# USBDAC_pcm2706.net
KiCad netlist of a schematic drawn in Altium Designer
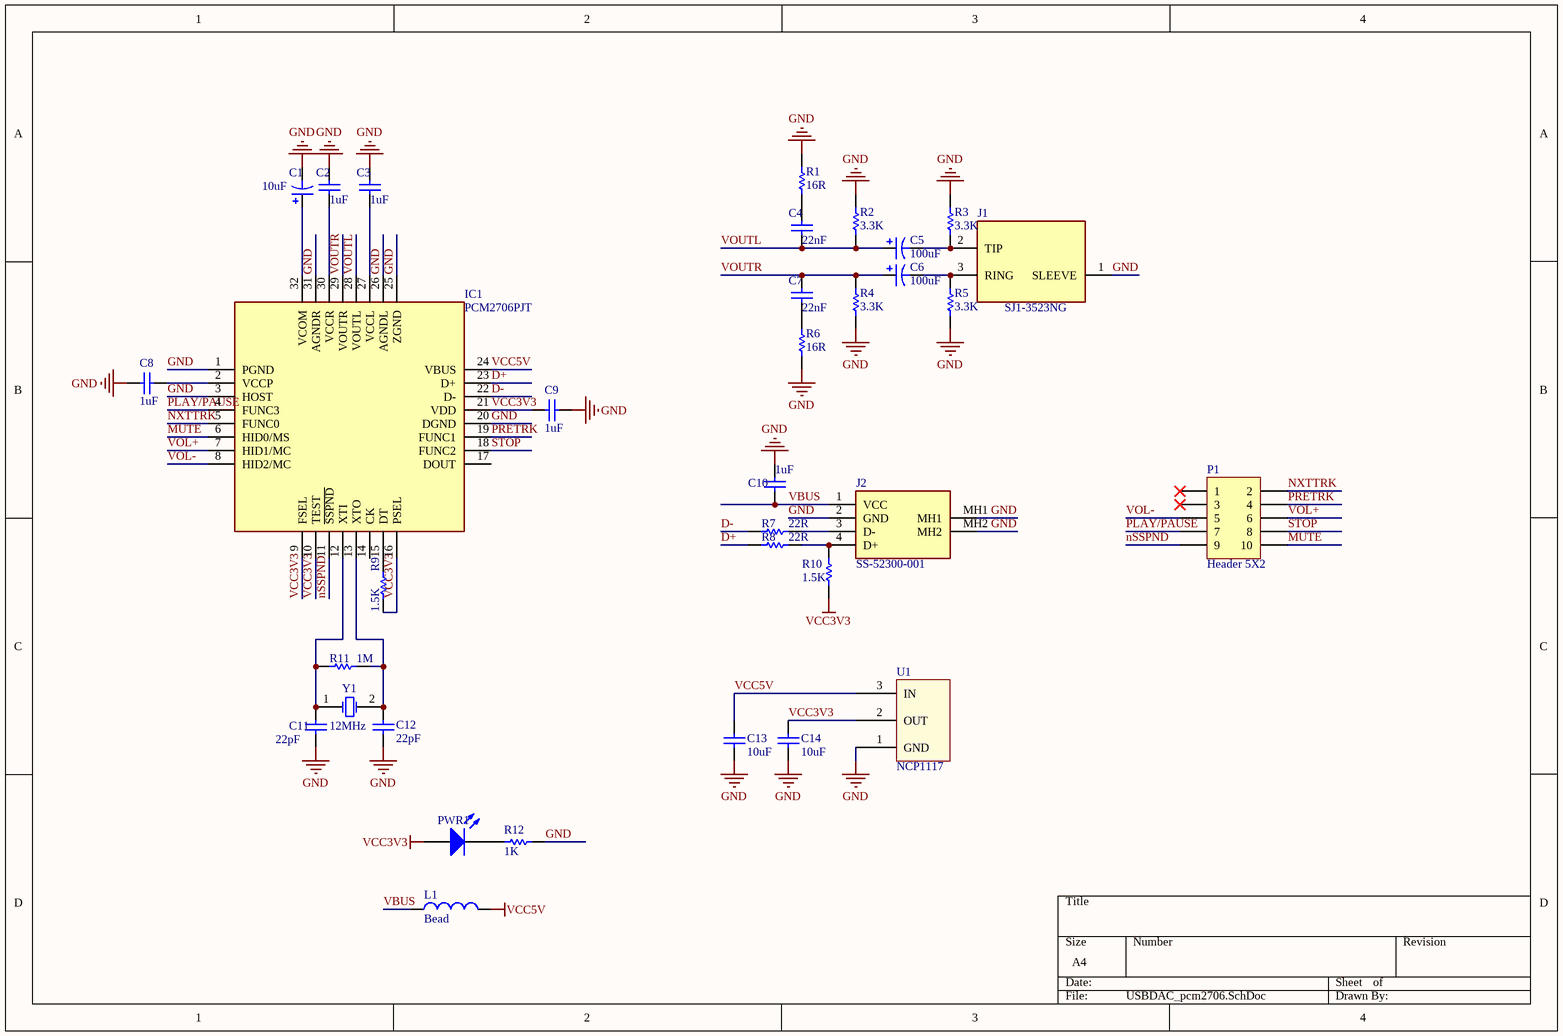
[diagram p0: USBDAC_pcm2706.SchDoc]

(export (version "E")
  (design (tool "Eeschema 10.0.6"))
  (components
    (comp (ref "C1")
      (value "10uF")
      (footprint "dip_cap")
      (description "Polarized Capacitor (Radial)")
      (fields (field (name "PUBLISHER") "Altium Limited"))
      (libsource (lib "Miscellaneous Devices") (part "Cap Pol1"))
    )
    (comp (ref "C2")
      (value "1uF")
      (footprint "SMD0805_CAP")
      (description "Capacitor (Semiconductor SIM Model)")
      (fields (field (name "PUBLISHER") "Altium Limited"))
      (libsource (lib "Miscellaneous Devices") (part "Cap Semi"))
    )
    (comp (ref "C3")
      (value "1uF")
      (footprint "SMD0805_CAP")
      (description "Capacitor (Semiconductor SIM Model)")
      (fields (field (name "PUBLISHER") "Altium Limited"))
      (libsource (lib "Miscellaneous Devices") (part "Cap Semi"))
    )
    (comp (ref "C4")
      (value "22nF")
      (footprint "SMD0805_CAP")
      (description "Capacitor (Semiconductor SIM Model)")
      (fields (field (name "PUBLISHER") "Altium Limited"))
      (libsource (lib "Miscellaneous Devices") (part "Cap Semi"))
    )
    (comp (ref "C5")
      (value "100uF")
      (footprint "dip_cap")
      (description "Polarized Capacitor (Radial)")
      (fields (field (name "PUBLISHER") "Altium Limited"))
      (libsource (lib "Miscellaneous Devices") (part "Cap Pol1"))
    )
    (comp (ref "C6")
      (value "100uF")
      (footprint "dip_cap")
      (description "Polarized Capacitor (Radial)")
      (fields (field (name "PUBLISHER") "Altium Limited"))
      (libsource (lib "Miscellaneous Devices") (part "Cap Pol1"))
    )
    (comp (ref "C7")
      (value "22nF")
      (footprint "SMD0805_CAP")
      (description "Capacitor (Semiconductor SIM Model)")
      (fields (field (name "PUBLISHER") "Altium Limited"))
      (libsource (lib "Miscellaneous Devices") (part "Cap Semi"))
    )
    (comp (ref "C8")
      (value "1uF")
      (footprint "SMD0805_CAP")
      (description "Capacitor (Semiconductor SIM Model)")
      (fields (field (name "PUBLISHER") "Altium Limited"))
      (libsource (lib "Miscellaneous Devices") (part "Cap Semi"))
    )
    (comp (ref "C9")
      (value "1uF")
      (footprint "SMD0805_CAP")
      (description "Capacitor (Semiconductor SIM Model)")
      (fields (field (name "PUBLISHER") "Altium Limited"))
      (libsource (lib "Miscellaneous Devices") (part "Cap Semi"))
    )
    (comp (ref "C10")
      (value "1uF")
      (footprint "SMD0805_CAP")
      (description "Capacitor (Semiconductor SIM Model)")
      (fields (field (name "PUBLISHER") "Altium Limited"))
      (libsource (lib "Miscellaneous Devices") (part "Cap Semi"))
    )
    (comp (ref "C11")
      (value "22pF")
      (footprint "SMD0805_CAP")
      (description "Capacitor (Semiconductor SIM Model)")
      (fields (field (name "PUBLISHER") "Altium Limited"))
      (libsource (lib "Miscellaneous Devices") (part "Cap Semi"))
    )
    (comp (ref "C12")
      (value "22pF")
      (footprint "SMD0805_CAP")
      (description "Capacitor (Semiconductor SIM Model)")
      (fields (field (name "PUBLISHER") "Altium Limited"))
      (libsource (lib "Miscellaneous Devices") (part "Cap Semi"))
    )
    (comp (ref "C13")
      (value "10uF")
      (footprint "SMD0805_CAP")
      (description "Capacitor (Semiconductor SIM Model)")
      (fields (field (name "PUBLISHER") "Altium Limited"))
      (libsource (lib "Miscellaneous Devices") (part "Cap Semi"))
    )
    (comp (ref "C14")
      (value "10uF")
      (footprint "SMD0805_CAP")
      (description "Capacitor (Semiconductor SIM Model)")
      (fields (field (name "PUBLISHER") "Altium Limited"))
      (libsource (lib "Miscellaneous Devices") (part "Cap Semi"))
    )
    (comp (ref "IC1")
      (value "PCM2706PJT")
      (footprint "usbdac_lib:QFP80P900X900X120-32N")
      (description "Integrated Circuit")
      (libsource (lib "usbdac_lib") (part "PCM2706PJT"))
    )
    (comp (ref "J1")
      (value "SJ1-3523NG")
      (footprint "usbdac_lib:SJ13523NG")
      (description "Connector")
      (libsource (lib "usbdac_lib") (part "SJ1-3523NG"))
    )
    (comp (ref "J2")
      (value "SS-52300-001")
      (footprint "usbdac_lib:SS52300001")
      (description "Connector")
      (libsource (lib "usbdac_lib") (part "SS-52300-001"))
    )
    (comp (ref "L1")
      (value "Bead")
      (footprint "SMD0805")
      (description "Inductor")
      (fields (field (name "PUBLISHER") "Altium Limited"))
      (libsource (lib "Miscellaneous Devices") (part "Inductor"))
    )
    (comp (ref "P1")
      (value "Header 5X2")
      (footprint "HDR2X5")
      (description "Header, 5-Pin, Dual row")
      (fields (field (name "PUBLISHER") "Altium Limited"))
      (libsource (lib "Miscellaneous Connectors") (part "Header 5X2"))
    )
    (comp (ref "PWR1")
      (value "LED0")
      (footprint "LED")
      (description "Typical INFRARED GaAs LED")
      (fields (field (name "PUBLISHER") "Altium Limited"))
      (libsource (lib "Miscellaneous Devices") (part "LED0"))
    )
    (comp (ref "R1")
      (value "16R")
      (footprint "SMD0805")
      (description "Semiconductor Resistor")
      (fields (field (name "Comment") "1K") (field (name "PUBLISHER") "Altium Limited"))
      (libsource (lib "Miscellaneous Devices") (part "Res Semi"))
    )
    (comp (ref "R2")
      (value "3.3K")
      (footprint "SMD0805")
      (description "Semiconductor Resistor")
      (fields (field (name "PUBLISHER") "Altium Limited"))
      (libsource (lib "Miscellaneous Devices") (part "Res Semi"))
    )
    (comp (ref "R3")
      (value "3.3K")
      (footprint "SMD0805")
      (description "Semiconductor Resistor")
      (fields (field (name "PUBLISHER") "Altium Limited"))
      (libsource (lib "Miscellaneous Devices") (part "Res Semi"))
    )
    (comp (ref "R4")
      (value "3.3K")
      (footprint "SMD0805")
      (description "Semiconductor Resistor")
      (fields (field (name "PUBLISHER") "Altium Limited"))
      (libsource (lib "Miscellaneous Devices") (part "Res Semi"))
    )
    (comp (ref "R5")
      (value "3.3K")
      (footprint "SMD0805")
      (description "Semiconductor Resistor")
      (fields (field (name "PUBLISHER") "Altium Limited"))
      (libsource (lib "Miscellaneous Devices") (part "Res Semi"))
    )
    (comp (ref "R6")
      (value "16R")
      (footprint "SMD0805")
      (description "Semiconductor Resistor")
      (fields (field (name "Comment") "1K") (field (name "PUBLISHER") "Altium Limited"))
      (libsource (lib "Miscellaneous Devices") (part "Res Semi"))
    )
    (comp (ref "R7")
      (value "22R")
      (footprint "SMD0805")
      (description "Semiconductor Resistor")
      (fields (field (name "PUBLISHER") "Altium Limited"))
      (libsource (lib "Miscellaneous Devices") (part "Res Semi"))
    )
    (comp (ref "R8")
      (value "22R")
      (footprint "SMD0805")
      (description "Semiconductor Resistor")
      (fields (field (name "PUBLISHER") "Altium Limited"))
      (libsource (lib "Miscellaneous Devices") (part "Res Semi"))
    )
    (comp (ref "R9")
      (value "1.5K")
      (footprint "SMD0805")
      (description "Semiconductor Resistor")
      (fields (field (name "PUBLISHER") "Altium Limited"))
      (libsource (lib "Miscellaneous Devices") (part "Res Semi"))
    )
    (comp (ref "R10")
      (value "1.5K")
      (footprint "SMD0805")
      (description "Semiconductor Resistor")
      (fields (field (name "PUBLISHER") "Altium Limited"))
      (libsource (lib "Miscellaneous Devices") (part "Res Semi"))
    )
    (comp (ref "R11")
      (value "1M")
      (footprint "SMD0805")
      (description "Semiconductor Resistor")
      (fields (field (name "PUBLISHER") "Altium Limited"))
      (libsource (lib "Miscellaneous Devices") (part "Res Semi"))
    )
    (comp (ref "R12")
      (value "1K")
      (footprint "SMD0805")
      (description "Semiconductor Resistor")
      (fields (field (name "PUBLISHER") "Altium Limited"))
      (libsource (lib "Miscellaneous Devices") (part "Res Semi"))
    )
    (comp (ref "U1")
      (value "NCP1117")
      (footprint "SOT-223-2")
      (description "IC REG 5V 1A DPAC")
      (libsource (lib "stm32_m3_component") (part "NCP1117"))
    )
    (comp (ref "Y1")
      (value "12MHz")
      (footprint "XTAL_DIP")
      (description "Crystal Oscillator 8MHz")
      (fields (field (name "PUBLISHER") "Altium Limited"))
      (libsource (lib "Miscellaneous Devices") (part "XTAL"))
    )
  )
  (nets
    (net (code "1") (name "/D+") (class "Default")
      (node (ref "IC1") (pin "23") (pinfunction "D+_23") (pintype "passive"))
      (node (ref "R8") (pin "1") (pinfunction "1_1") (pintype "passive"))
    )
    (net (code "2") (name "/D-") (class "Default")
      (node (ref "IC1") (pin "22") (pinfunction "D-_22") (pintype "passive"))
      (node (ref "R7") (pin "1") (pinfunction "1_1") (pintype "passive"))
    )
    (net (code "3") (name "/MUTE") (class "Default")
      (node (ref "IC1") (pin "6") (pinfunction "HID0/MS_6") (pintype "passive"))
      (node (ref "P1") (pin "10") (pinfunction "10_10") (pintype "passive"))
    )
    (net (code "4") (name "/NXTTRK") (class "Default")
      (node (ref "IC1") (pin "5") (pinfunction "FUNC0_5") (pintype "passive"))
      (node (ref "P1") (pin "2") (pinfunction "2_2") (pintype "passive"))
    )
    (net (code "5") (name "/PLAY{slash}PAUSE") (class "Default")
      (node (ref "IC1") (pin "4") (pinfunction "FUNC3_4") (pintype "passive"))
      (node (ref "P1") (pin "7") (pinfunction "7_7") (pintype "passive"))
    )
    (net (code "6") (name "/PRETRK") (class "Default")
      (node (ref "IC1") (pin "19") (pinfunction "FUNC1_19") (pintype "passive"))
      (node (ref "P1") (pin "4") (pinfunction "4_4") (pintype "passive"))
    )
    (net (code "7") (name "/STOP") (class "Default")
      (node (ref "IC1") (pin "18") (pinfunction "FUNC2_18") (pintype "passive"))
      (node (ref "P1") (pin "8") (pinfunction "8_8") (pintype "passive"))
    )
    (net (code "8") (name "/VBUS") (class "Default")
      (node (ref "C10") (pin "2") (pinfunction "2_2") (pintype "passive"))
      (node (ref "J2") (pin "1") (pinfunction "VCC_1") (pintype "passive"))
      (node (ref "L1") (pin "1") (pinfunction "1_1") (pintype "passive"))
    )
    (net (code "9") (name "/VOL+") (class "Default")
      (node (ref "IC1") (pin "7") (pinfunction "HID1/MC_7") (pintype "passive"))
      (node (ref "P1") (pin "6") (pinfunction "6_6") (pintype "passive"))
    )
    (net (code "10") (name "/VOL-") (class "Default")
      (node (ref "IC1") (pin "8") (pinfunction "HID2/MC_8") (pintype "passive"))
      (node (ref "P1") (pin "5") (pinfunction "5_5") (pintype "passive"))
    )
    (net (code "11") (name "/VOUTL") (class "Default")
      (node (ref "C4") (pin "1") (pinfunction "1_1") (pintype "passive"))
      (node (ref "C5") (pin "1") (pinfunction "1_1") (pintype "passive"))
      (node (ref "IC1") (pin "28") (pinfunction "VOUTL_28") (pintype "passive"))
      (node (ref "R2") (pin "1") (pinfunction "1_1") (pintype "passive"))
    )
    (net (code "12") (name "/VOUTR") (class "Default")
      (node (ref "C6") (pin "1") (pinfunction "1_1") (pintype "passive"))
      (node (ref "C7") (pin "1") (pinfunction "1_1") (pintype "passive"))
      (node (ref "IC1") (pin "29") (pinfunction "VOUTR_29") (pintype "passive"))
      (node (ref "R4") (pin "2") (pinfunction "2_2") (pintype "passive"))
    )
    (net (code "13") (name "/nSSPND") (class "Default")
      (node (ref "IC1") (pin "11") (pinfunction "~{SSPND}_11") (pintype "passive"))
      (node (ref "P1") (pin "9") (pinfunction "9_9") (pintype "passive"))
    )
    (net (code "14") (name "GND") (class "Default")
      (node (ref "C1") (pin "2") (pinfunction "2_2") (pintype "passive"))
      (node (ref "C10") (pin "1") (pinfunction "1_1") (pintype "passive"))
      (node (ref "C11") (pin "2") (pinfunction "2_2") (pintype "passive"))
      (node (ref "C12") (pin "2") (pinfunction "2_2") (pintype "passive"))
      (node (ref "C13") (pin "1") (pinfunction "1_1") (pintype "passive"))
      (node (ref "C14") (pin "1") (pinfunction "1_1") (pintype "passive"))
      (node (ref "C2") (pin "1") (pinfunction "1_1") (pintype "passive"))
      (node (ref "C3") (pin "1") (pinfunction "1_1") (pintype "passive"))
      (node (ref "C8") (pin "1") (pinfunction "1_1") (pintype "passive"))
      (node (ref "C9") (pin "1") (pinfunction "1_1") (pintype "passive"))
      (node (ref "IC1") (pin "1") (pinfunction "PGND_1") (pintype "passive"))
      (node (ref "IC1") (pin "20") (pinfunction "DGND_20") (pintype "passive"))
      (node (ref "IC1") (pin "25") (pinfunction "ZGND_25") (pintype "passive"))
      (node (ref "IC1") (pin "26") (pinfunction "AGNDL_26") (pintype "passive"))
      (node (ref "IC1") (pin "3") (pinfunction "HOST_3") (pintype "passive"))
      (node (ref "IC1") (pin "31") (pinfunction "AGNDR_31") (pintype "passive"))
      (node (ref "J1") (pin "1") (pinfunction "SLEEVE_1") (pintype "passive"))
      (node (ref "J2") (pin "2") (pinfunction "GND_2") (pintype "passive"))
      (node (ref "J2") (pin "MH1") (pinfunction "MH1_MH1") (pintype "passive"))
      (node (ref "J2") (pin "MH2") (pinfunction "MH2_MH2") (pintype "passive"))
      (node (ref "R1") (pin "2") (pinfunction "2_2") (pintype "passive"))
      (node (ref "R12") (pin "1") (pinfunction "1_1") (pintype "passive"))
      (node (ref "R2") (pin "2") (pinfunction "2_2") (pintype "passive"))
      (node (ref "R3") (pin "2") (pinfunction "2_2") (pintype "passive"))
      (node (ref "R4") (pin "1") (pinfunction "1_1") (pintype "passive"))
      (node (ref "R5") (pin "1") (pinfunction "1_1") (pintype "passive"))
      (node (ref "R6") (pin "2") (pinfunction "2_2") (pintype "passive"))
      (node (ref "U1") (pin "1") (pinfunction "GND_1") (pintype "passive"))
    )
    (net (code "15") (name "Net-(C4-Pad2)") (class "Default")
      (node (ref "C4") (pin "2") (pinfunction "2_2") (pintype "passive"))
      (node (ref "R1") (pin "1") (pinfunction "1_1") (pintype "passive"))
    )
    (net (code "16") (name "Net-(C7-Pad2)") (class "Default")
      (node (ref "C7") (pin "2") (pinfunction "2_2") (pintype "passive"))
      (node (ref "R6") (pin "1") (pinfunction "1_1") (pintype "passive"))
    )
    (net (code "17") (name "Net-(IC1-DT)") (class "Default")
      (node (ref "IC1") (pin "15") (pinfunction "DT_15") (pintype "passive"))
      (node (ref "R9") (pin "2") (pinfunction "2_2") (pintype "passive"))
    )
    (net (code "18") (name "Net-(IC1-VCCL)") (class "Default")
      (node (ref "C3") (pin "2") (pinfunction "2_2") (pintype "passive"))
      (node (ref "IC1") (pin "27") (pinfunction "VCCL_27") (pintype "passive"))
    )
    (net (code "19") (name "Net-(IC1-VCCP)") (class "Default")
      (node (ref "C8") (pin "2") (pinfunction "2_2") (pintype "passive"))
      (node (ref "IC1") (pin "2") (pinfunction "VCCP_2") (pintype "passive"))
    )
    (net (code "20") (name "Net-(IC1-VCCR)") (class "Default")
      (node (ref "C2") (pin "2") (pinfunction "2_2") (pintype "passive"))
      (node (ref "IC1") (pin "30") (pinfunction "VCCR_30") (pintype "passive"))
    )
    (net (code "21") (name "Net-(IC1-VCOM)") (class "Default")
      (node (ref "C1") (pin "1") (pinfunction "1_1") (pintype "passive"))
      (node (ref "IC1") (pin "32") (pinfunction "VCOM_32") (pintype "passive"))
    )
    (net (code "22") (name "Net-(IC1-XTI)") (class "Default")
      (node (ref "C11") (pin "1") (pinfunction "1_1") (pintype "passive"))
      (node (ref "IC1") (pin "12") (pinfunction "XTI_12") (pintype "passive"))
      (node (ref "R11") (pin "1") (pinfunction "1_1") (pintype "passive"))
      (node (ref "Y1") (pin "1") (pinfunction "OSC1_1") (pintype "passive"))
    )
    (net (code "23") (name "Net-(IC1-XTO)") (class "Default")
      (node (ref "C12") (pin "1") (pinfunction "1_1") (pintype "passive"))
      (node (ref "IC1") (pin "13") (pinfunction "XTO_13") (pintype "passive"))
      (node (ref "R11") (pin "2") (pinfunction "2_2") (pintype "passive"))
      (node (ref "Y1") (pin "2") (pinfunction "OSC2_2") (pintype "passive"))
    )
    (net (code "24") (name "Net-(J1-RING)") (class "Default")
      (node (ref "C6") (pin "2") (pinfunction "2_2") (pintype "passive"))
      (node (ref "J1") (pin "3") (pinfunction "RING_3") (pintype "passive"))
      (node (ref "R5") (pin "2") (pinfunction "2_2") (pintype "passive"))
    )
    (net (code "25") (name "Net-(J1-TIP)") (class "Default")
      (node (ref "C5") (pin "2") (pinfunction "2_2") (pintype "passive"))
      (node (ref "J1") (pin "2") (pinfunction "TIP_2") (pintype "passive"))
      (node (ref "R3") (pin "1") (pinfunction "1_1") (pintype "passive"))
    )
    (net (code "26") (name "Net-(J2-D+)") (class "Default")
      (node (ref "J2") (pin "4") (pinfunction "D+_4") (pintype "passive"))
      (node (ref "R10") (pin "2") (pinfunction "2_2") (pintype "passive"))
      (node (ref "R8") (pin "2") (pinfunction "2_2") (pintype "passive"))
    )
    (net (code "27") (name "Net-(J2-D-)") (class "Default")
      (node (ref "J2") (pin "3") (pinfunction "D-_3") (pintype "passive"))
      (node (ref "R7") (pin "2") (pinfunction "2_2") (pintype "passive"))
    )
    (net (code "28") (name "Net-(PWR1-K)") (class "Default")
      (node (ref "PWR1") (pin "2") (pinfunction "K_2") (pintype "passive"))
      (node (ref "R12") (pin "2") (pinfunction "2_2") (pintype "passive"))
    )
    (net (code "29") (name "VCC3V3") (class "Default")
      (node (ref "C14") (pin "2") (pinfunction "2_2") (pintype "passive"))
      (node (ref "C9") (pin "2") (pinfunction "2_2") (pintype "passive"))
      (node (ref "IC1") (pin "10") (pinfunction "TEST_10") (pintype "passive"))
      (node (ref "IC1") (pin "16") (pinfunction "PSEL_16") (pintype "passive"))
      (node (ref "IC1") (pin "21") (pinfunction "VDD_21") (pintype "passive"))
      (node (ref "IC1") (pin "9") (pinfunction "FSEL_9") (pintype "passive"))
      (node (ref "PWR1") (pin "1") (pinfunction "A_1") (pintype "passive"))
      (node (ref "R10") (pin "1") (pinfunction "1_1") (pintype "passive"))
      (node (ref "R9") (pin "1") (pinfunction "1_1") (pintype "passive"))
      (node (ref "U1") (pin "2") (pinfunction "OUT_2") (pintype "passive"))
    )
    (net (code "30") (name "VCC5V") (class "Default")
      (node (ref "C13") (pin "2") (pinfunction "2_2") (pintype "passive"))
      (node (ref "IC1") (pin "24") (pinfunction "VBUS_24") (pintype "passive"))
      (node (ref "L1") (pin "2") (pinfunction "2_2") (pintype "passive"))
      (node (ref "U1") (pin "3") (pinfunction "IN_3") (pintype "passive"))
    )
    (net (code "31") (name "unconnected-(IC1-CK-Pad14)") (class "Default")
      (node (ref "IC1") (pin "14") (pinfunction "CK_14") (pintype "passive"))
    )
    (net (code "32") (name "unconnected-(IC1-DOUT-Pad17)") (class "Default")
      (node (ref "IC1") (pin "17") (pinfunction "DOUT_17") (pintype "passive"))
    )
    (net (code "33") (name "unconnected-(P1-Pad1)") (class "Default")
      (node (ref "P1") (pin "1") (pinfunction "1_1") (pintype "passive+no_connect"))
    )
    (net (code "34") (name "unconnected-(P1-Pad3)") (class "Default")
      (node (ref "P1") (pin "3") (pinfunction "3_3") (pintype "passive+no_connect"))
    )
  )
)
